# Charger600.net
KiCad netlist of a schematic drawn in Altium Designer
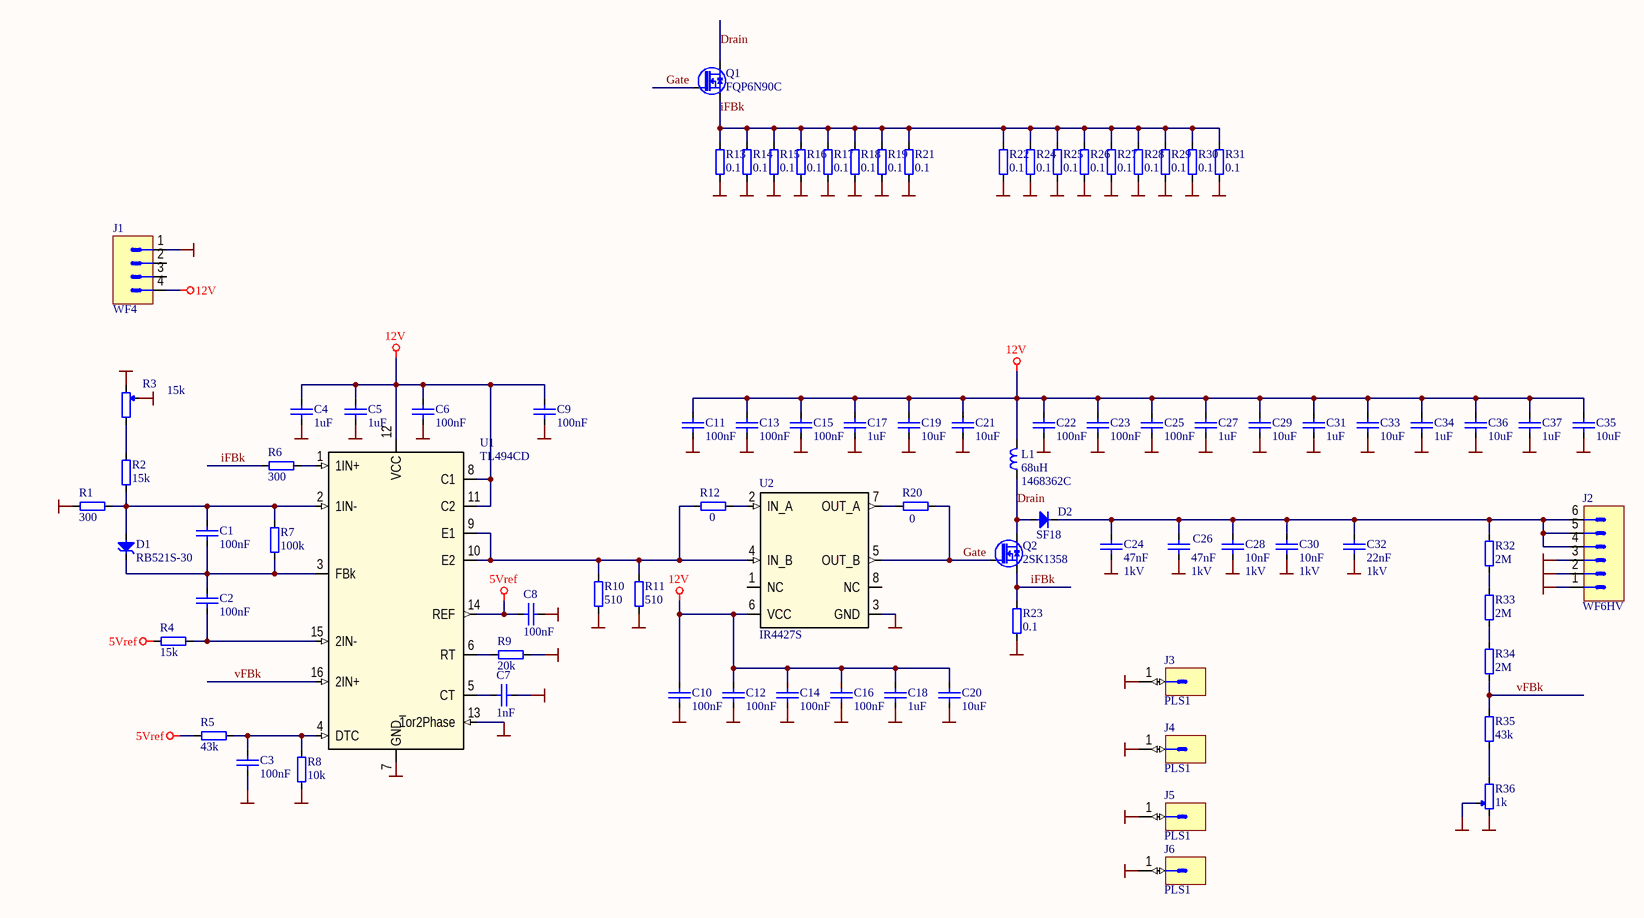
[diagram p0: Charger600.SchDoc]

(export (version "E")
  (design (tool "Eeschema 10.0.6"))
  (components
    (comp (ref "C1")
      (value "100nF")
      (footprint "CAPC1608X87N")
      (description "Чип конденсатор 0603")
      (fields (field (name "VOLTAGE") "50V") (field (name "TOLERANCE") "20%"))
      (libsource (lib "DDSintLib") (part "C0603"))
    )
    (comp (ref "C2")
      (value "100nF")
      (footprint "CAPC1608X87N")
      (description "Чип конденсатор 0603")
      (fields (field (name "VOLTAGE") "50V") (field (name "TOLERANCE") "20%"))
      (libsource (lib "DDSintLib") (part "C0603"))
    )
    (comp (ref "C3")
      (value "100nF")
      (footprint "CAPC1608X87N")
      (description "Чип конденсатор 0603")
      (fields (field (name "VOLTAGE") "50V") (field (name "TOLERANCE") "20%"))
      (libsource (lib "DDSintLib") (part "C0603"))
    )
    (comp (ref "C4")
      (value "1uF")
      (footprint "SMD0805CAP")
      (description "Чип конденсатор 0805")
      (fields (field (name "VOLTAGE") "25V") (field (name "TOLERANCE") "20%"))
      (libsource (lib "DDSintLib") (part "C0805"))
    )
    (comp (ref "C5")
      (value "1uF")
      (footprint "SMD0805CAP")
      (description "Чип конденсатор 0805")
      (fields (field (name "VOLTAGE") "25V") (field (name "TOLERANCE") "20%"))
      (libsource (lib "DDSintLib") (part "C0805"))
    )
    (comp (ref "C6")
      (value "100nF")
      (footprint "CAPC1608X87N")
      (description "Чип конденсатор 0603")
      (fields (field (name "VOLTAGE") "50V") (field (name "TOLERANCE") "20%"))
      (libsource (lib "DDSintLib") (part "C0603"))
    )
    (comp (ref "C7")
      (value "1nF")
      (footprint "CAPC1608X87N")
      (description "Чип конденсатор 0603")
      (fields (field (name "VOLTAGE") "50V") (field (name "TOLERANCE") "20%"))
      (libsource (lib "DDSintLib") (part "C0603"))
    )
    (comp (ref "C8")
      (value "100nF")
      (footprint "CAPC1608X87N")
      (description "Чип конденсатор 0603")
      (fields (field (name "VOLTAGE") "50V") (field (name "TOLERANCE") "20%"))
      (libsource (lib "DDSintLib") (part "C0603"))
    )
    (comp (ref "C9")
      (value "100nF")
      (footprint "CAPC1608X87N")
      (description "Чип конденсатор 0603")
      (fields (field (name "VOLTAGE") "50V") (field (name "TOLERANCE") "20%"))
      (libsource (lib "DDSintLib") (part "C0603"))
    )
    (comp (ref "C10")
      (value "100nF")
      (footprint "CAPC1608X87N")
      (description "Чип конденсатор 0603")
      (fields (field (name "VOLTAGE") "50V") (field (name "TOLERANCE") "20%"))
      (libsource (lib "DDSintLib") (part "C0603"))
    )
    (comp (ref "C11")
      (value "100nF")
      (footprint "CAPC1608X87N")
      (description "Чип конденсатор 0603")
      (fields (field (name "VOLTAGE") "50V") (field (name "TOLERANCE") "20%"))
      (libsource (lib "DDSintLib") (part "C0603"))
    )
    (comp (ref "C12")
      (value "100nF")
      (footprint "CAPC1608X87N")
      (description "Чип конденсатор 0603")
      (fields (field (name "VOLTAGE") "50V") (field (name "TOLERANCE") "20%"))
      (libsource (lib "DDSintLib") (part "C0603"))
    )
    (comp (ref "C13")
      (value "100nF")
      (footprint "CAPC1608X87N")
      (description "Чип конденсатор 0603")
      (fields (field (name "VOLTAGE") "50V") (field (name "TOLERANCE") "20%"))
      (libsource (lib "DDSintLib") (part "C0603"))
    )
    (comp (ref "C14")
      (value "100nF")
      (footprint "CAPC1608X87N")
      (description "Чип конденсатор 0603")
      (fields (field (name "VOLTAGE") "50V") (field (name "TOLERANCE") "20%"))
      (libsource (lib "DDSintLib") (part "C0603"))
    )
    (comp (ref "C15")
      (value "100nF")
      (footprint "CAPC1608X87N")
      (description "Чип конденсатор 0603")
      (fields (field (name "VOLTAGE") "50V") (field (name "TOLERANCE") "20%"))
      (libsource (lib "DDSintLib") (part "C0603"))
    )
    (comp (ref "C16")
      (value "100nF")
      (footprint "CAPC1608X87N")
      (description "Чип конденсатор 0603")
      (fields (field (name "VOLTAGE") "50V") (field (name "TOLERANCE") "20%"))
      (libsource (lib "DDSintLib") (part "C0603"))
    )
    (comp (ref "C17")
      (value "1uF")
      (footprint "SMD0805CAP")
      (description "Чип конденсатор 0805")
      (fields (field (name "VOLTAGE") "25V") (field (name "TOLERANCE") "20%"))
      (libsource (lib "DDSintLib") (part "C0805"))
    )
    (comp (ref "C18")
      (value "1uF")
      (footprint "SMD0805CAP")
      (description "Чип конденсатор 0805")
      (fields (field (name "VOLTAGE") "25V") (field (name "TOLERANCE") "20%"))
      (libsource (lib "DDSintLib") (part "C0805"))
    )
    (comp (ref "C19")
      (value "10uF")
      (footprint "CAPC1206")
      (description "Чип конденсатор 1206")
      (fields (field (name "VOLTAGE") "25V") (field (name "TOLERANCE") "1%"))
      (libsource (lib "DDS1") (part "C1206"))
    )
    (comp (ref "C20")
      (value "10uF")
      (footprint "CAPC1206")
      (description "Чип конденсатор 1206")
      (fields (field (name "VOLTAGE") "25V") (field (name "TOLERANCE") "1%"))
      (libsource (lib "DDS1") (part "C1206"))
    )
    (comp (ref "C21")
      (value "10uF")
      (footprint "CAPC1206")
      (description "Чип конденсатор 1206")
      (fields (field (name "VOLTAGE") "25V") (field (name "TOLERANCE") "1%"))
      (libsource (lib "DDS1") (part "C1206"))
    )
    (comp (ref "C22")
      (value "100nF")
      (footprint "CAPC1608X87N")
      (description "Чип конденсатор 0603")
      (fields (field (name "VOLTAGE") "50V") (field (name "TOLERANCE") "20%"))
      (libsource (lib "DDSintLib") (part "C0603"))
    )
    (comp (ref "C23")
      (value "100nF")
      (footprint "CAPC1608X87N")
      (description "Чип конденсатор 0603")
      (fields (field (name "VOLTAGE") "50V") (field (name "TOLERANCE") "20%"))
      (libsource (lib "DDSintLib") (part "C0603"))
    )
    (comp (ref "C24")
      (value "47nF")
      (footprint "CAPR2750-900X3150X1900")
      (description "HV THD capacitor")
      (fields (field (name "TOLERANCE") "+-10%") (field (name "VOLTAGE") "1kV"))
      (libsource (lib "DDSintLib") (part "CBB81"))
    )
    (comp (ref "C25")
      (value "100nF")
      (footprint "CAPC1608X87N")
      (description "Чип конденсатор 0603")
      (fields (field (name "VOLTAGE") "50V") (field (name "TOLERANCE") "20%"))
      (libsource (lib "DDSintLib") (part "C0603"))
    )
    (comp (ref "C26")
      (value "47nF")
      (footprint "CAPR2750-900X3150X1900")
      (description "HV THD capacitor")
      (fields (field (name "TOLERANCE") "+-10%") (field (name "VOLTAGE") "1kV"))
      (libsource (lib "DDSintLib") (part "CBB81"))
    )
    (comp (ref "C27")
      (value "1uF")
      (footprint "SMD0805CAP")
      (description "Чип конденсатор 0805")
      (fields (field (name "VOLTAGE") "25V") (field (name "TOLERANCE") "20%"))
      (libsource (lib "DDSintLib") (part "C0805"))
    )
    (comp (ref "C28")
      (value "10nF")
      (footprint "CAPR1500-900X1800X1750")
      (description "HV THD capacitor")
      (fields (field (name "TOLERANCE") "+-10%") (field (name "VOLTAGE") "1kV"))
      (libsource (lib "DDSintLib") (part "CK45-B3AD"))
    )
    (comp (ref "C29")
      (value "10uF")
      (footprint "CAPC1206")
      (description "Чип конденсатор 1206")
      (fields (field (name "VOLTAGE") "25V") (field (name "TOLERANCE") "1%"))
      (libsource (lib "DDS1") (part "C1206"))
    )
    (comp (ref "C30")
      (value "10nF")
      (footprint "CAPR1500-900X1800X1750")
      (description "HV THD capacitor")
      (fields (field (name "TOLERANCE") "+-10%") (field (name "VOLTAGE") "1kV"))
      (libsource (lib "DDSintLib") (part "CK45-B3AD"))
    )
    (comp (ref "C31")
      (value "1uF")
      (footprint "SMD0805CAP")
      (description "Чип конденсатор 0805")
      (fields (field (name "VOLTAGE") "25V") (field (name "TOLERANCE") "20%"))
      (libsource (lib "DDSintLib") (part "C0805"))
    )
    (comp (ref "C32")
      (value "22nF")
      (footprint "CAPR2250-900X2600X1850")
      (description "HV THD capacitor")
      (fields (field (name "TOLERANCE") "+-10%") (field (name "VOLTAGE") "1kV"))
      (libsource (lib "DDSintLib") (part "CT-81"))
    )
    (comp (ref "C33")
      (value "10uF")
      (footprint "CAPC1206")
      (description "Чип конденсатор 1206")
      (fields (field (name "VOLTAGE") "25V") (field (name "TOLERANCE") "1%"))
      (libsource (lib "DDS1") (part "C1206"))
    )
    (comp (ref "C34")
      (value "1uF")
      (footprint "SMD0805CAP")
      (description "Чип конденсатор 0805")
      (fields (field (name "VOLTAGE") "25V") (field (name "TOLERANCE") "20%"))
      (libsource (lib "DDSintLib") (part "C0805"))
    )
    (comp (ref "C35")
      (value "10uF")
      (footprint "CAPC1206")
      (description "Чип конденсатор 1206")
      (fields (field (name "VOLTAGE") "25V") (field (name "TOLERANCE") "1%"))
      (libsource (lib "DDS1") (part "C1206"))
    )
    (comp (ref "C36")
      (value "10uF")
      (footprint "CAPC1206")
      (description "Чип конденсатор 1206")
      (fields (field (name "VOLTAGE") "25V") (field (name "TOLERANCE") "1%"))
      (libsource (lib "DDS1") (part "C1206"))
    )
    (comp (ref "C37")
      (value "1uF")
      (footprint "SMD0805CAP")
      (description "Чип конденсатор 0805")
      (fields (field (name "VOLTAGE") "25V") (field (name "TOLERANCE") "20%"))
      (libsource (lib "DDSintLib") (part "C0805"))
    )
    (comp (ref "D1")
      (value "RB521S-30")
      (footprint "SODFL1608X65N")
      (description "Чип Шоттки диод")
      (fields (field (name "VOLTAGE") "30V"))
      (libsource (lib "DDSintLib") (part "RB521S-30"))
    )
    (comp (ref "D2")
      (value "SF18")
      (footprint "DIOAD1397W120L700D400")
      (description "HV fast diode")
      (fields (field (name "VOLTAGE") "800"))
      (libsource (lib "DDS1") (part "SF18"))
    )
    (comp (ref "J1")
      (value "WF4")
      (footprint "WF4_2_54")
      (description "Вилка  WF4")
      (libsource (lib "DDSintLib") (part "WF4"))
    )
    (comp (ref "J2")
      (value "WF6HV")
      (footprint "MOLEX_WF6HV")
      (description "Вилка  WF6 HV")
      (libsource (lib "DDSintLib") (part "WF6HV"))
    )
    (comp (ref "J3")
      (value "PLS1")
      (footprint "PLS1")
      (description "Штырь PLS1")
      (libsource (lib "DDSintLib") (part "PLS1"))
    )
    (comp (ref "J4")
      (value "PLS1")
      (footprint "PLS1")
      (description "Штырь PLS1")
      (libsource (lib "DDSintLib") (part "PLS1"))
    )
    (comp (ref "J5")
      (value "PLS1")
      (footprint "PLS1")
      (description "Штырь PLS1")
      (libsource (lib "DDSintLib") (part "PLS1"))
    )
    (comp (ref "J6")
      (value "PLS1")
      (footprint "PLS1")
      (description "Штырь PLS1")
      (libsource (lib "DDSintLib") (part "PLS1"))
    )
    (comp (ref "L1")
      (value "68uH")
      (footprint "muR1468362C")
      (description "THD inductor")
      (fields (field (name "TOLERANCE") "20%") (field (name "DEVICE") "1468362С"))
      (libsource (lib "DDSintLib") (part "1468362С"))
    )
    (comp (ref "Q1")
      (value "FQP6N90C")
      (footprint "TO-220-v")
      (description "NMOS")
      (fields (field (name "VOLTAGE") "900V"))
      (libsource (lib "DDS1") (part "FQP6N90C"))
    )
    (comp (ref "Q2")
      (value "2SK1358")
      (footprint "TO-247-v")
      (description "NMOS")
      (fields (field (name "VOLTAGE") "900V"))
      (libsource (lib "DDS1") (part "2SK1358"))
    )
    (comp (ref "R1")
      (value "300")
      (footprint "RESC1608X64N")
      (description "Чип резистор 0603")
      (fields (field (name "TOLERANCE") "1%"))
      (libsource (lib "DDSintLib") (part "R0603"))
    )
    (comp (ref "R2")
      (value "15k")
      (footprint "RESC1608X64N")
      (description "Чип резистор 0603")
      (fields (field (name "TOLERANCE") "1%"))
      (libsource (lib "DDSintLib") (part "R0603"))
    )
    (comp (ref "R3")
      (value "15k")
      (footprint "TRIM_BOURNS_3296Y")
      (description "Trimmer Potentiometer")
      (libsource (lib "DDSintLib") (part "3296"))
    )
    (comp (ref "R4")
      (value "15k")
      (footprint "RESC1608X64N")
      (description "Чип резистор 0603")
      (fields (field (name "TOLERANCE") "1%"))
      (libsource (lib "DDSintLib") (part "R0603"))
    )
    (comp (ref "R5")
      (value "43k")
      (footprint "RESC1608X64N")
      (description "Чип резистор 0603")
      (fields (field (name "TOLERANCE") "1%"))
      (libsource (lib "DDSintLib") (part "R0603"))
    )
    (comp (ref "R6")
      (value "300")
      (footprint "RESC1608X64N")
      (description "Чип резистор 0603")
      (fields (field (name "TOLERANCE") "1%"))
      (libsource (lib "DDSintLib") (part "R0603"))
    )
    (comp (ref "R7")
      (value "100k")
      (footprint "RESC1608X64N")
      (description "Чип резистор 0603")
      (fields (field (name "TOLERANCE") "1%"))
      (libsource (lib "DDSintLib") (part "R0603"))
    )
    (comp (ref "R8")
      (value "10k")
      (footprint "RESC1608X64N")
      (description "Чип резистор 0603")
      (fields (field (name "TOLERANCE") "1%"))
      (libsource (lib "DDSintLib") (part "R0603"))
    )
    (comp (ref "R9")
      (value "20k")
      (footprint "RESC1608X64N")
      (description "Чип резистор 0603")
      (fields (field (name "TOLERANCE") "1%"))
      (libsource (lib "DDSintLib") (part "R0603"))
    )
    (comp (ref "R10")
      (value "510")
      (footprint "RESC3016X65N")
      (description "Чип резистор 1206")
      (fields (field (name "TOLERANCE") "1%"))
      (libsource (lib "DDSintLib") (part "R1206"))
    )
    (comp (ref "R11")
      (value "510")
      (footprint "RESC3016X65N")
      (description "Чип резистор 1206")
      (fields (field (name "TOLERANCE") "1%"))
      (libsource (lib "DDSintLib") (part "R1206"))
    )
    (comp (ref "R12")
      (value "0")
      (footprint "RESC1608X64N")
      (description "Чип резистор 0603")
      (fields (field (name "TOLERANCE") "1%"))
      (libsource (lib "DDSintLib") (part "R0603"))
    )
    (comp (ref "R13")
      (value "0.1")
      (footprint "SMD0805RES")
      (description "Чип резистор 0805")
      (fields (field (name "TOLERANCE") "1%"))
      (libsource (lib "DDSintLib") (part "R0805"))
    )
    (comp (ref "R14")
      (value "0.1")
      (footprint "SMD0805RES")
      (description "Чип резистор 0805")
      (fields (field (name "TOLERANCE") "1%"))
      (libsource (lib "DDSintLib") (part "R0805"))
    )
    (comp (ref "R15")
      (value "0.1")
      (footprint "SMD0805RES")
      (description "Чип резистор 0805")
      (fields (field (name "TOLERANCE") "1%"))
      (libsource (lib "DDSintLib") (part "R0805"))
    )
    (comp (ref "R16")
      (value "0.1")
      (footprint "SMD0805RES")
      (description "Чип резистор 0805")
      (fields (field (name "TOLERANCE") "1%"))
      (libsource (lib "DDSintLib") (part "R0805"))
    )
    (comp (ref "R17")
      (value "0.1")
      (footprint "SMD0805RES")
      (description "Чип резистор 0805")
      (fields (field (name "TOLERANCE") "1%"))
      (libsource (lib "DDSintLib") (part "R0805"))
    )
    (comp (ref "R18")
      (value "0.1")
      (footprint "SMD0805RES")
      (description "Чип резистор 0805")
      (fields (field (name "TOLERANCE") "1%"))
      (libsource (lib "DDSintLib") (part "R0805"))
    )
    (comp (ref "R19")
      (value "0.1")
      (footprint "SMD0805RES")
      (description "Чип резистор 0805")
      (fields (field (name "TOLERANCE") "1%"))
      (libsource (lib "DDSintLib") (part "R0805"))
    )
    (comp (ref "R20")
      (value "0")
      (footprint "RESC1608X64N")
      (description "Чип резистор 0603")
      (fields (field (name "TOLERANCE") "1%"))
      (libsource (lib "DDSintLib") (part "R0603"))
    )
    (comp (ref "R21")
      (value "0.1")
      (footprint "SMD0805RES")
      (description "Чип резистор 0805")
      (fields (field (name "TOLERANCE") "1%"))
      (libsource (lib "DDSintLib") (part "R0805"))
    )
    (comp (ref "R22")
      (value "0.1")
      (footprint "RESC3016X65N")
      (description "Чип резистор 1206")
      (fields (field (name "TOLERANCE") "1%"))
      (libsource (lib "DDSintLib") (part "R1206"))
    )
    (comp (ref "R23")
      (value "0.1")
      (footprint "SMD0805RES")
      (description "Чип резистор 0805")
      (fields (field (name "TOLERANCE") "1%"))
      (libsource (lib "DDSintLib") (part "R0805"))
    )
    (comp (ref "R24")
      (value "0.1")
      (footprint "RESC3016X65N")
      (description "Чип резистор 1206")
      (fields (field (name "TOLERANCE") "1%"))
      (libsource (lib "DDSintLib") (part "R1206"))
    )
    (comp (ref "R25")
      (value "0.1")
      (footprint "RESC3016X65N")
      (description "Чип резистор 1206")
      (fields (field (name "TOLERANCE") "1%"))
      (libsource (lib "DDSintLib") (part "R1206"))
    )
    (comp (ref "R26")
      (value "0.1")
      (footprint "RESC3016X65N")
      (description "Чип резистор 1206")
      (fields (field (name "TOLERANCE") "1%"))
      (libsource (lib "DDSintLib") (part "R1206"))
    )
    (comp (ref "R27")
      (value "0.1")
      (footprint "RESC3016X65N")
      (description "Чип резистор 1206")
      (fields (field (name "TOLERANCE") "1%"))
      (libsource (lib "DDSintLib") (part "R1206"))
    )
    (comp (ref "R28")
      (value "0.1")
      (footprint "RESC3016X65N")
      (description "Чип резистор 1206")
      (fields (field (name "TOLERANCE") "1%"))
      (libsource (lib "DDSintLib") (part "R1206"))
    )
    (comp (ref "R29")
      (value "0.1")
      (footprint "RESC3016X65N")
      (description "Чип резистор 1206")
      (fields (field (name "TOLERANCE") "1%"))
      (libsource (lib "DDSintLib") (part "R1206"))
    )
    (comp (ref "R30")
      (value "0.1")
      (footprint "RESC3016X65N")
      (description "Чип резистор 1206")
      (fields (field (name "TOLERANCE") "1%"))
      (libsource (lib "DDSintLib") (part "R1206"))
    )
    (comp (ref "R31")
      (value "0.1")
      (footprint "RESC3016X65N")
      (description "Чип резистор 1206")
      (fields (field (name "TOLERANCE") "1%"))
      (libsource (lib "DDSintLib") (part "R1206"))
    )
    (comp (ref "R32")
      (value "2M")
      (footprint "RES1016-360X210")
      (description "250mW THD resistor")
      (fields (field (name "TOLERANCE") "1%"))
      (libsource (lib "DDSintLib") (part "CF-1/4W"))
    )
    (comp (ref "R33")
      (value "2M")
      (footprint "RES1016-360X210")
      (description "250mW THD resistor")
      (fields (field (name "TOLERANCE") "1%"))
      (libsource (lib "DDSintLib") (part "CF-1/4W"))
    )
    (comp (ref "R34")
      (value "2M")
      (footprint "RES1016-360X210")
      (description "250mW THD resistor")
      (fields (field (name "TOLERANCE") "1%"))
      (libsource (lib "DDSintLib") (part "CF-1/4W"))
    )
    (comp (ref "R35")
      (value "43k")
      (footprint "RESC1608X64N")
      (description "Чип резистор 0603")
      (fields (field (name "TOLERANCE") "1%"))
      (libsource (lib "DDSintLib") (part "R0603"))
    )
    (comp (ref "R36")
      (value "1k")
      (footprint "TRIM_BOURNS_3296Y")
      (description "Trimmer Potentiometer")
      (libsource (lib "DDSintLib") (part "3296"))
    )
    (comp (ref "U1")
      (value "TL494CD")
      (footprint "SOIC127P780X200-16N")
      (description "PWM Controller")
      (libsource (lib "DDS1") (part "TL494"))
    )
    (comp (ref "U2")
      (value "IR4427S")
      (footprint "SOIC127P600X175-8N")
      (description "Double low side non inverting MOSFET driver")
      (libsource (lib "DDS1") (part "IR4427"))
    )
  )
  (nets
    (net (code "1") (name "/Drain") (class "Default")
      (node (ref "D2") (pin "2") (pinfunction "A_2") (pintype "passive"))
      (node (ref "L1") (pin "1") (pinfunction "1_1") (pintype "passive"))
      (node (ref "Q1") (pin "2") (pinfunction "D_2") (pintype "passive"))
      (node (ref "Q2") (pin "2") (pinfunction "D_2") (pintype "passive"))
    )
    (net (code "2") (name "/Gate") (class "Default")
      (node (ref "Q1") (pin "1") (pinfunction "G_1") (pintype "passive"))
      (node (ref "Q2") (pin "1") (pinfunction "G_1") (pintype "passive"))
      (node (ref "R20") (pin "2") (pinfunction "2_2") (pintype "passive"))
      (node (ref "U2") (pin "5") (pinfunction "OUT_B_5") (pintype "output"))
    )
    (net (code "3") (name "/iFBk") (class "Default")
      (node (ref "Q1") (pin "3") (pinfunction "S_3") (pintype "passive"))
      (node (ref "Q2") (pin "3") (pinfunction "S_3") (pintype "passive"))
      (node (ref "R13") (pin "2") (pinfunction "2_2") (pintype "passive"))
      (node (ref "R14") (pin "2") (pinfunction "2_2") (pintype "passive"))
      (node (ref "R15") (pin "2") (pinfunction "2_2") (pintype "passive"))
      (node (ref "R16") (pin "2") (pinfunction "2_2") (pintype "passive"))
      (node (ref "R17") (pin "2") (pinfunction "2_2") (pintype "passive"))
      (node (ref "R18") (pin "2") (pinfunction "2_2") (pintype "passive"))
      (node (ref "R19") (pin "2") (pinfunction "2_2") (pintype "passive"))
      (node (ref "R21") (pin "2") (pinfunction "2_2") (pintype "passive"))
      (node (ref "R22") (pin "2") (pinfunction "2_2") (pintype "passive"))
      (node (ref "R23") (pin "2") (pinfunction "2_2") (pintype "passive"))
      (node (ref "R24") (pin "2") (pinfunction "2_2") (pintype "passive"))
      (node (ref "R25") (pin "2") (pinfunction "2_2") (pintype "passive"))
      (node (ref "R26") (pin "2") (pinfunction "2_2") (pintype "passive"))
      (node (ref "R27") (pin "2") (pinfunction "2_2") (pintype "passive"))
      (node (ref "R28") (pin "2") (pinfunction "2_2") (pintype "passive"))
      (node (ref "R29") (pin "2") (pinfunction "2_2") (pintype "passive"))
      (node (ref "R30") (pin "2") (pinfunction "2_2") (pintype "passive"))
      (node (ref "R31") (pin "2") (pinfunction "2_2") (pintype "passive"))
      (node (ref "R6") (pin "2") (pinfunction "2_2") (pintype "passive"))
    )
    (net (code "4") (name "/vFBk") (class "Default")
      (node (ref "R34") (pin "1") (pinfunction "1_1") (pintype "passive"))
      (node (ref "R35") (pin "2") (pinfunction "2_2") (pintype "passive"))
      (node (ref "U1") (pin "16") (pinfunction "2IN+_16") (pintype "input"))
    )
    (net (code "5") (name "5Vref") (class "Default")
      (node (ref "C8") (pin "2") (pinfunction "2_2") (pintype "passive"))
      (node (ref "R4") (pin "2") (pinfunction "2_2") (pintype "passive"))
      (node (ref "R5") (pin "2") (pinfunction "2_2") (pintype "passive"))
      (node (ref "U1") (pin "14") (pinfunction "REF_14") (pintype "output"))
    )
    (net (code "6") (name "12V") (class "Default")
      (node (ref "C10") (pin "2") (pinfunction "2_2") (pintype "passive"))
      (node (ref "C11") (pin "2") (pinfunction "2_2") (pintype "passive"))
      (node (ref "C12") (pin "2") (pinfunction "2_2") (pintype "passive"))
      (node (ref "C13") (pin "2") (pinfunction "2_2") (pintype "passive"))
      (node (ref "C14") (pin "2") (pinfunction "2_2") (pintype "passive"))
      (node (ref "C15") (pin "2") (pinfunction "2_2") (pintype "passive"))
      (node (ref "C16") (pin "2") (pinfunction "2_2") (pintype "passive"))
      (node (ref "C17") (pin "2") (pinfunction "2_2") (pintype "passive"))
      (node (ref "C18") (pin "2") (pinfunction "2_2") (pintype "passive"))
      (node (ref "C19") (pin "2") (pinfunction "2_2") (pintype "passive"))
      (node (ref "C20") (pin "2") (pinfunction "2_2") (pintype "passive"))
      (node (ref "C21") (pin "2") (pinfunction "2_2") (pintype "passive"))
      (node (ref "C22") (pin "2") (pinfunction "2_2") (pintype "passive"))
      (node (ref "C23") (pin "2") (pinfunction "2_2") (pintype "passive"))
      (node (ref "C25") (pin "2") (pinfunction "2_2") (pintype "passive"))
      (node (ref "C27") (pin "2") (pinfunction "2_2") (pintype "passive"))
      (node (ref "C29") (pin "2") (pinfunction "2_2") (pintype "passive"))
      (node (ref "C31") (pin "2") (pinfunction "2_2") (pintype "passive"))
      (node (ref "C33") (pin "2") (pinfunction "2_2") (pintype "passive"))
      (node (ref "C34") (pin "2") (pinfunction "2_2") (pintype "passive"))
      (node (ref "C35") (pin "2") (pinfunction "2_2") (pintype "passive"))
      (node (ref "C36") (pin "2") (pinfunction "2_2") (pintype "passive"))
      (node (ref "C37") (pin "2") (pinfunction "2_2") (pintype "passive"))
      (node (ref "C4") (pin "2") (pinfunction "2_2") (pintype "passive"))
      (node (ref "C5") (pin "2") (pinfunction "2_2") (pintype "passive"))
      (node (ref "C6") (pin "2") (pinfunction "2_2") (pintype "passive"))
      (node (ref "C9") (pin "2") (pinfunction "2_2") (pintype "passive"))
      (node (ref "J1") (pin "4") (pinfunction "4_4") (pintype "bidirectional"))
      (node (ref "L1") (pin "2") (pinfunction "2_2") (pintype "passive"))
      (node (ref "U1") (pin "11") (pinfunction "C2_11") (pintype "open_collector"))
      (node (ref "U1") (pin "12") (pinfunction "VCC_12") (pintype "power_in"))
      (node (ref "U1") (pin "8") (pinfunction "C1_8") (pintype "open_collector"))
      (node (ref "U2") (pin "6") (pinfunction "VCC_6") (pintype "power_in"))
    )
    (net (code "7") (name "GND") (class "Default")
      (node (ref "C10") (pin "1") (pinfunction "1_1") (pintype "passive"))
      (node (ref "C11") (pin "1") (pinfunction "1_1") (pintype "passive"))
      (node (ref "C12") (pin "1") (pinfunction "1_1") (pintype "passive"))
      (node (ref "C13") (pin "1") (pinfunction "1_1") (pintype "passive"))
      (node (ref "C14") (pin "1") (pinfunction "1_1") (pintype "passive"))
      (node (ref "C15") (pin "1") (pinfunction "1_1") (pintype "passive"))
      (node (ref "C16") (pin "1") (pinfunction "1_1") (pintype "passive"))
      (node (ref "C17") (pin "1") (pinfunction "1_1") (pintype "passive"))
      (node (ref "C18") (pin "1") (pinfunction "1_1") (pintype "passive"))
      (node (ref "C19") (pin "1") (pinfunction "1_1") (pintype "passive"))
      (node (ref "C20") (pin "1") (pinfunction "1_1") (pintype "passive"))
      (node (ref "C21") (pin "1") (pinfunction "1_1") (pintype "passive"))
      (node (ref "C22") (pin "1") (pinfunction "1_1") (pintype "passive"))
      (node (ref "C23") (pin "1") (pinfunction "1_1") (pintype "passive"))
      (node (ref "C24") (pin "1") (pinfunction "1_1") (pintype "passive"))
      (node (ref "C25") (pin "1") (pinfunction "1_1") (pintype "passive"))
      (node (ref "C26") (pin "1") (pinfunction "1_1") (pintype "passive"))
      (node (ref "C27") (pin "1") (pinfunction "1_1") (pintype "passive"))
      (node (ref "C28") (pin "1") (pinfunction "1_1") (pintype "passive"))
      (node (ref "C29") (pin "1") (pinfunction "1_1") (pintype "passive"))
      (node (ref "C3") (pin "1") (pinfunction "1_1") (pintype "passive"))
      (node (ref "C30") (pin "1") (pinfunction "1_1") (pintype "passive"))
      (node (ref "C31") (pin "1") (pinfunction "1_1") (pintype "passive"))
      (node (ref "C32") (pin "1") (pinfunction "1_1") (pintype "passive"))
      (node (ref "C33") (pin "1") (pinfunction "1_1") (pintype "passive"))
      (node (ref "C34") (pin "1") (pinfunction "1_1") (pintype "passive"))
      (node (ref "C35") (pin "1") (pinfunction "1_1") (pintype "passive"))
      (node (ref "C36") (pin "1") (pinfunction "1_1") (pintype "passive"))
      (node (ref "C37") (pin "1") (pinfunction "1_1") (pintype "passive"))
      (node (ref "C4") (pin "1") (pinfunction "1_1") (pintype "passive"))
      (node (ref "C5") (pin "1") (pinfunction "1_1") (pintype "passive"))
      (node (ref "C6") (pin "1") (pinfunction "1_1") (pintype "passive"))
      (node (ref "C7") (pin "1") (pinfunction "1_1") (pintype "passive"))
      (node (ref "C8") (pin "1") (pinfunction "1_1") (pintype "passive"))
      (node (ref "C9") (pin "1") (pinfunction "1_1") (pintype "passive"))
      (node (ref "J1") (pin "1") (pinfunction "1_1") (pintype "bidirectional"))
      (node (ref "J2") (pin "1") (pinfunction "1_1") (pintype "bidirectional"))
      (node (ref "J2") (pin "2") (pinfunction "2_2") (pintype "bidirectional"))
      (node (ref "J2") (pin "3") (pinfunction "3_3") (pintype "bidirectional"))
      (node (ref "J3") (pin "1") (pinfunction "1_1") (pintype "bidirectional"))
      (node (ref "J4") (pin "1") (pinfunction "1_1") (pintype "bidirectional"))
      (node (ref "J5") (pin "1") (pinfunction "1_1") (pintype "bidirectional"))
      (node (ref "J6") (pin "1") (pinfunction "1_1") (pintype "bidirectional"))
      (node (ref "R1") (pin "2") (pinfunction "2_2") (pintype "passive"))
      (node (ref "R10") (pin "1") (pinfunction "1_1") (pintype "passive"))
      (node (ref "R11") (pin "1") (pinfunction "1_1") (pintype "passive"))
      (node (ref "R13") (pin "1") (pinfunction "1_1") (pintype "passive"))
      (node (ref "R14") (pin "1") (pinfunction "1_1") (pintype "passive"))
      (node (ref "R15") (pin "1") (pinfunction "1_1") (pintype "passive"))
      (node (ref "R16") (pin "1") (pinfunction "1_1") (pintype "passive"))
      (node (ref "R17") (pin "1") (pinfunction "1_1") (pintype "passive"))
      (node (ref "R18") (pin "1") (pinfunction "1_1") (pintype "passive"))
      (node (ref "R19") (pin "1") (pinfunction "1_1") (pintype "passive"))
      (node (ref "R21") (pin "1") (pinfunction "1_1") (pintype "passive"))
      (node (ref "R22") (pin "1") (pinfunction "1_1") (pintype "passive"))
      (node (ref "R23") (pin "1") (pinfunction "1_1") (pintype "passive"))
      (node (ref "R24") (pin "1") (pinfunction "1_1") (pintype "passive"))
      (node (ref "R25") (pin "1") (pinfunction "1_1") (pintype "passive"))
      (node (ref "R26") (pin "1") (pinfunction "1_1") (pintype "passive"))
      (node (ref "R27") (pin "1") (pinfunction "1_1") (pintype "passive"))
      (node (ref "R28") (pin "1") (pinfunction "1_1") (pintype "passive"))
      (node (ref "R29") (pin "1") (pinfunction "1_1") (pintype "passive"))
      (node (ref "R3") (pin "1") (pinfunction "1_1") (pintype "passive"))
      (node (ref "R3") (pin "2") (pinfunction "W_2") (pintype "passive"))
      (node (ref "R30") (pin "1") (pinfunction "1_1") (pintype "passive"))
      (node (ref "R31") (pin "1") (pinfunction "1_1") (pintype "passive"))
      (node (ref "R36") (pin "1") (pinfunction "1_1") (pintype "passive"))
      (node (ref "R36") (pin "2") (pinfunction "W_2") (pintype "passive"))
      (node (ref "R8") (pin "1") (pinfunction "1_1") (pintype "passive"))
      (node (ref "R9") (pin "1") (pinfunction "1_1") (pintype "passive"))
      (node (ref "U1") (pin "13") (pinfunction "~{1}or2Phase_13") (pintype "input"))
      (node (ref "U1") (pin "7") (pinfunction "GND_7") (pintype "power_in"))
      (node (ref "U2") (pin "3") (pinfunction "GND_3") (pintype "power_in"))
    )
    (net (code "8") (name "Net-(D1-A)") (class "Default")
      (node (ref "C1") (pin "2") (pinfunction "2_2") (pintype "passive"))
      (node (ref "D1") (pin "2") (pinfunction "A_2") (pintype "passive"))
      (node (ref "R1") (pin "1") (pinfunction "1_1") (pintype "passive"))
      (node (ref "R2") (pin "1") (pinfunction "1_1") (pintype "passive"))
      (node (ref "R7") (pin "2") (pinfunction "2_2") (pintype "passive"))
      (node (ref "U1") (pin "2") (pinfunction "1IN-_2") (pintype "input"))
    )
    (net (code "9") (name "Net-(D1-C)") (class "Default")
      (node (ref "C1") (pin "1") (pinfunction "1_1") (pintype "passive"))
      (node (ref "C2") (pin "2") (pinfunction "2_2") (pintype "passive"))
      (node (ref "D1") (pin "1") (pinfunction "C_1") (pintype "passive"))
      (node (ref "R7") (pin "1") (pinfunction "1_1") (pintype "passive"))
      (node (ref "U1") (pin "3") (pinfunction "FBk_3") (pintype "passive"))
    )
    (net (code "10") (name "Net-(D2-C)") (class "Default")
      (node (ref "C24") (pin "2") (pinfunction "2_2") (pintype "passive"))
      (node (ref "C26") (pin "2") (pinfunction "2_2") (pintype "passive"))
      (node (ref "C28") (pin "2") (pinfunction "2_2") (pintype "passive"))
      (node (ref "C30") (pin "2") (pinfunction "2_2") (pintype "passive"))
      (node (ref "C32") (pin "2") (pinfunction "2_2") (pintype "passive"))
      (node (ref "D2") (pin "1") (pinfunction "C_1") (pintype "passive"))
      (node (ref "J2") (pin "4") (pinfunction "4_4") (pintype "bidirectional"))
      (node (ref "J2") (pin "5") (pinfunction "5_5") (pintype "bidirectional"))
      (node (ref "J2") (pin "6") (pinfunction "6_6") (pintype "bidirectional"))
      (node (ref "R32") (pin "2") (pinfunction "2_2") (pintype "passive"))
    )
    (net (code "11") (name "Net-(R2-Pad2)") (class "Default")
      (node (ref "R2") (pin "2") (pinfunction "2_2") (pintype "passive"))
      (node (ref "R3") (pin "3") (pinfunction "3_3") (pintype "passive"))
    )
    (net (code "12") (name "Net-(R32-Pad1)") (class "Default")
      (node (ref "R32") (pin "1") (pinfunction "1_1") (pintype "passive"))
      (node (ref "R33") (pin "2") (pinfunction "2_2") (pintype "passive"))
    )
    (net (code "13") (name "Net-(R33-Pad1)") (class "Default")
      (node (ref "R33") (pin "1") (pinfunction "1_1") (pintype "passive"))
      (node (ref "R34") (pin "2") (pinfunction "2_2") (pintype "passive"))
    )
    (net (code "14") (name "Net-(R35-Pad1)") (class "Default")
      (node (ref "R35") (pin "1") (pinfunction "1_1") (pintype "passive"))
      (node (ref "R36") (pin "3") (pinfunction "3_3") (pintype "passive"))
    )
    (net (code "15") (name "Net-(U1-1IN+)") (class "Default")
      (node (ref "R6") (pin "1") (pinfunction "1_1") (pintype "passive"))
      (node (ref "U1") (pin "1") (pinfunction "1IN+_1") (pintype "input"))
    )
    (net (code "16") (name "Net-(U1-2IN-)") (class "Default")
      (node (ref "C2") (pin "1") (pinfunction "1_1") (pintype "passive"))
      (node (ref "R4") (pin "1") (pinfunction "1_1") (pintype "passive"))
      (node (ref "U1") (pin "15") (pinfunction "2IN-_15") (pintype "input"))
    )
    (net (code "17") (name "Net-(U1-CT)") (class "Default")
      (node (ref "C7") (pin "2") (pinfunction "2_2") (pintype "passive"))
      (node (ref "U1") (pin "5") (pinfunction "CT_5") (pintype "passive"))
    )
    (net (code "18") (name "Net-(U1-DTC)") (class "Default")
      (node (ref "C3") (pin "2") (pinfunction "2_2") (pintype "passive"))
      (node (ref "R5") (pin "1") (pinfunction "1_1") (pintype "passive"))
      (node (ref "R8") (pin "2") (pinfunction "2_2") (pintype "passive"))
      (node (ref "U1") (pin "4") (pinfunction "DTC_4") (pintype "input"))
    )
    (net (code "19") (name "Net-(U1-E1)") (class "Default")
      (node (ref "R10") (pin "2") (pinfunction "2_2") (pintype "passive"))
      (node (ref "R11") (pin "2") (pinfunction "2_2") (pintype "passive"))
      (node (ref "R12") (pin "1") (pinfunction "1_1") (pintype "passive"))
      (node (ref "U1") (pin "10") (pinfunction "E2_10") (pintype "open_emitter"))
      (node (ref "U1") (pin "9") (pinfunction "E1_9") (pintype "open_emitter"))
      (node (ref "U2") (pin "4") (pinfunction "IN_B_4") (pintype "input"))
    )
    (net (code "20") (name "Net-(U1-RT)") (class "Default")
      (node (ref "R9") (pin "2") (pinfunction "2_2") (pintype "passive"))
      (node (ref "U1") (pin "6") (pinfunction "RT_6") (pintype "passive"))
    )
    (net (code "21") (name "Net-(U2-IN_A)") (class "Default")
      (node (ref "R12") (pin "2") (pinfunction "2_2") (pintype "passive"))
      (node (ref "U2") (pin "2") (pinfunction "IN_A_2") (pintype "input"))
    )
    (net (code "22") (name "Net-(U2-OUT_A)") (class "Default")
      (node (ref "R20") (pin "1") (pinfunction "1_1") (pintype "passive"))
      (node (ref "U2") (pin "7") (pinfunction "OUT_A_7") (pintype "output"))
    )
    (net (code "23") (name "unconnected-(J1-Pad2)") (class "Default")
      (node (ref "J1") (pin "2") (pinfunction "2_2") (pintype "bidirectional"))
    )
    (net (code "24") (name "unconnected-(J1-Pad3)") (class "Default")
      (node (ref "J1") (pin "3") (pinfunction "3_3") (pintype "bidirectional"))
    )
    (net (code "25") (name "unconnected-(U2-NC-Pad1)") (class "Default")
      (node (ref "U2") (pin "1") (pinfunction "NC_1") (pintype "passive"))
    )
    (net (code "26") (name "unconnected-(U2-NC-Pad8)") (class "Default")
      (node (ref "U2") (pin "8") (pinfunction "NC_8") (pintype "passive"))
    )
  )
)
